# NoTricks_v2.net
KiCad netlist of a schematic drawn in EAGLE
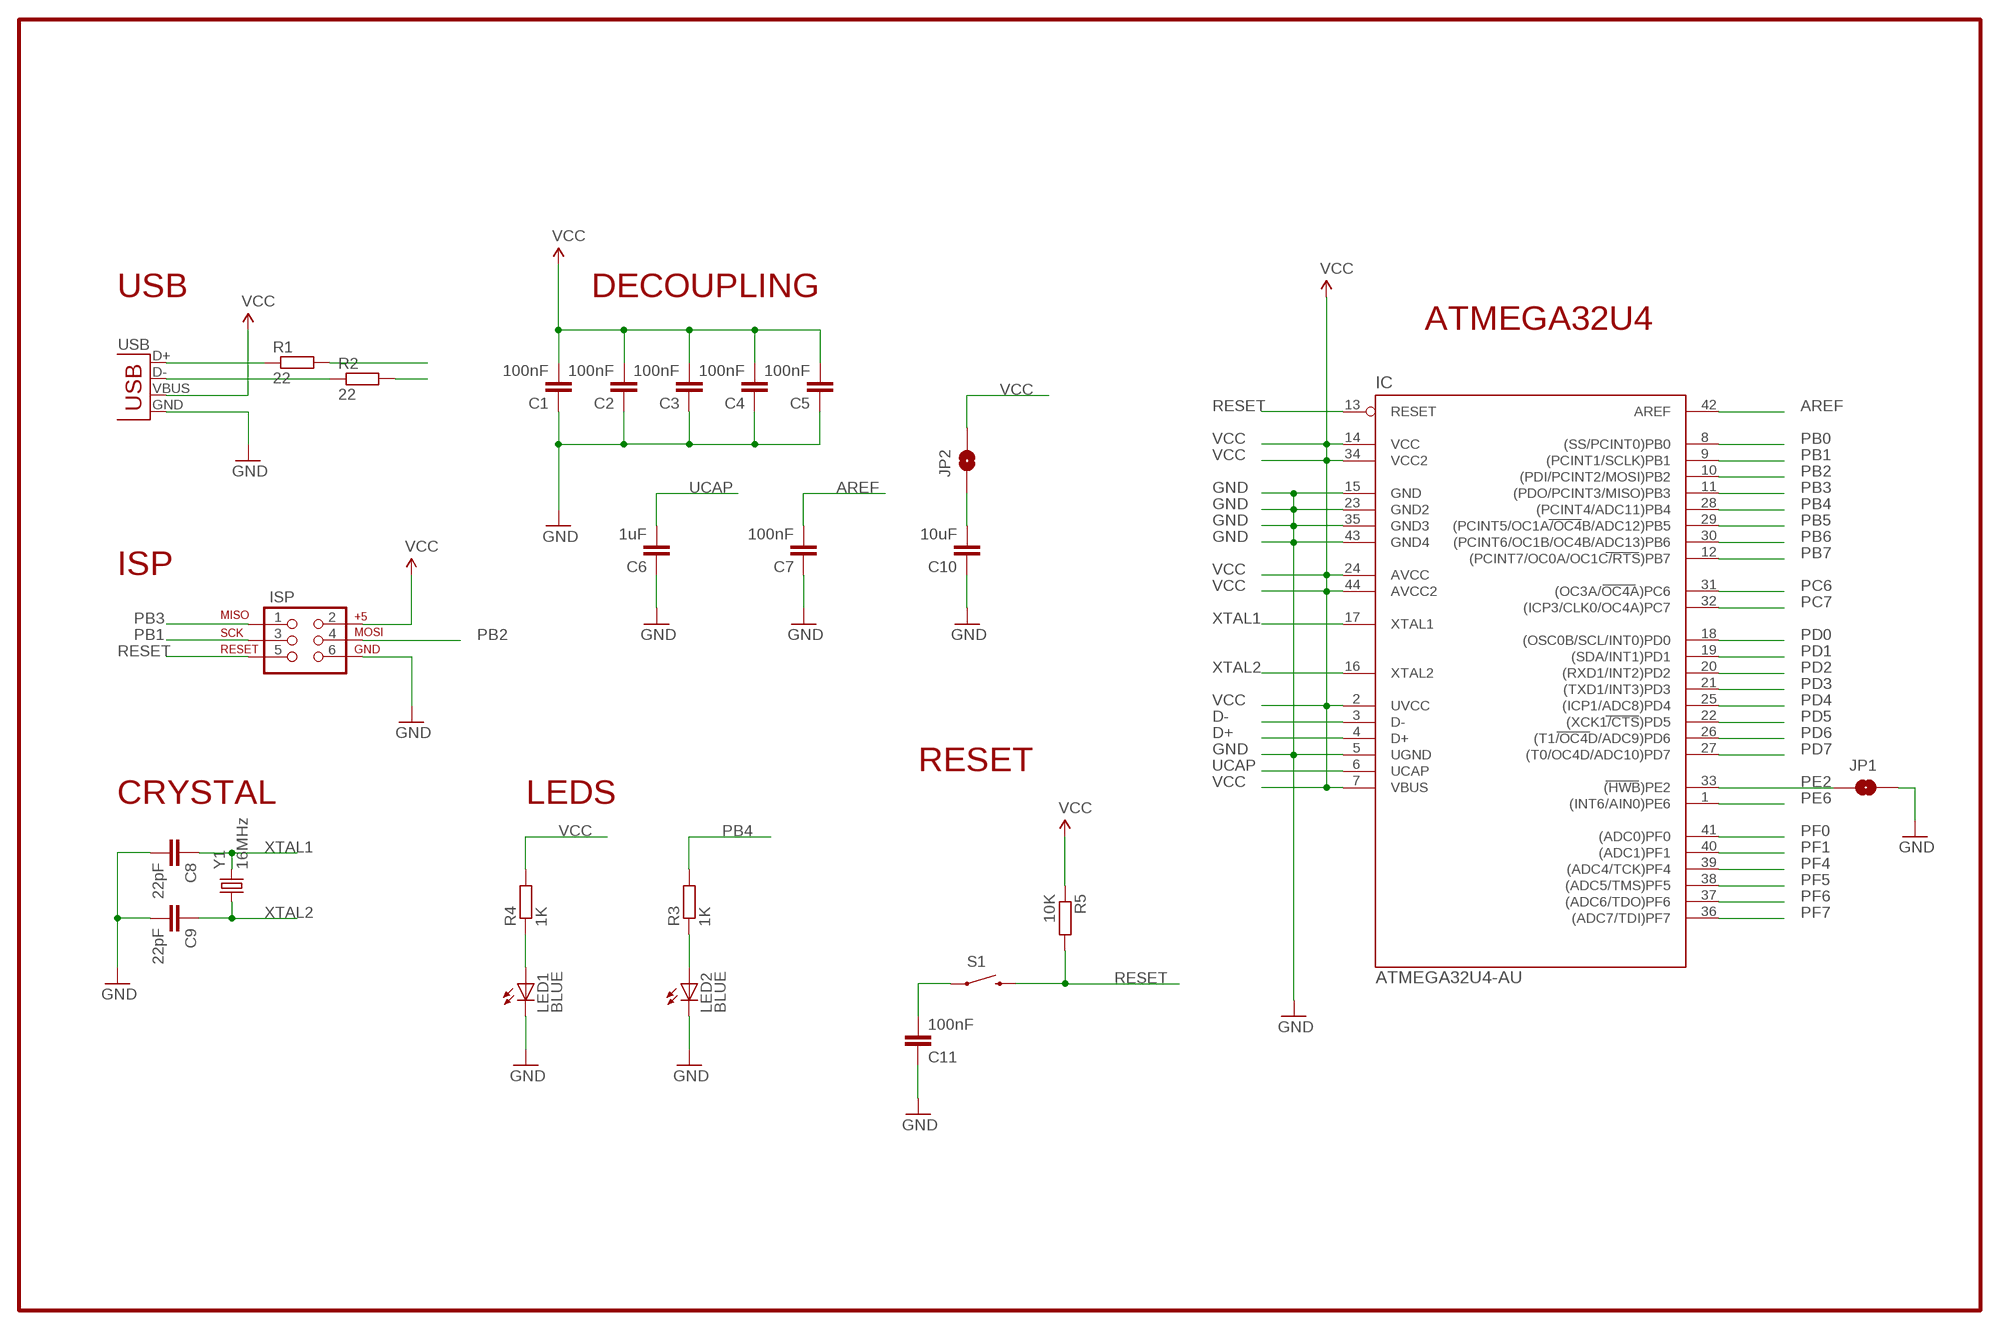
[diagram p0: schematic, sheet 1]

(export (version "E")
  (design (tool "Eeschema 10.0.6"))
  (components
    (comp (ref "C1")
      (value "100nF")
      (footprint "eagle-import:C0805")
      (libsource (lib "eagle-import") (part "C-EUC0805"))
    )
    (comp (ref "C2")
      (value "100nF")
      (footprint "eagle-import:C0805")
      (libsource (lib "eagle-import") (part "C-EUC0805"))
    )
    (comp (ref "C3")
      (value "100nF")
      (footprint "eagle-import:C0805")
      (libsource (lib "eagle-import") (part "C-EUC0805"))
    )
    (comp (ref "C4")
      (value "100nF")
      (footprint "eagle-import:C0805")
      (libsource (lib "eagle-import") (part "C-EUC0805"))
    )
    (comp (ref "C5")
      (value "100nF")
      (footprint "eagle-import:C0805")
      (libsource (lib "eagle-import") (part "C-EUC0805"))
    )
    (comp (ref "C6")
      (value "1uF")
      (footprint "eagle-import:C0805")
      (libsource (lib "eagle-import") (part "C-EUC0805"))
    )
    (comp (ref "C7")
      (value "100nF")
      (footprint "eagle-import:C0805")
      (libsource (lib "eagle-import") (part "C-EUC0805"))
    )
    (comp (ref "C8")
      (value "22pF")
      (footprint "eagle-import:C0805")
      (libsource (lib "eagle-import") (part "C-EUC0805"))
    )
    (comp (ref "C9")
      (value "22pF")
      (footprint "eagle-import:C0805")
      (libsource (lib "eagle-import") (part "C-EUC0805"))
    )
    (comp (ref "C10")
      (value "10uF")
      (footprint "eagle-import:C0805")
      (libsource (lib "eagle-import") (part "C-EUC0805"))
    )
    (comp (ref "C11")
      (value "100nF")
      (footprint "eagle-import:C0805")
      (libsource (lib "eagle-import") (part "C-EUC0805"))
    )
    (comp (ref "IC")
      (value "ATMEGA32U4-AU")
      (footprint "eagle-import:TQFP44")
      (libsource (lib "eagle-import") (part "ATMEGA32U4-AU"))
    )
    (comp (ref "ISP")
      (value "AVR_SPI_PRG_6PTH")
      (footprint "eagle-import:2X3")
      (libsource (lib "eagle-import") (part "AVR_SPI_PRG_6PTH"))
    )
    (comp (ref "JP1")
      (value "JUMPER-PAD-2-NO")
      (footprint "eagle-import:PAD-JUMPER-2-NO_NO_SILK")
      (libsource (lib "eagle-import") (part "JUMPER-PAD-2-NO"))
    )
    (comp (ref "JP2")
      (value "JUMPER-PAD-2-NO")
      (footprint "eagle-import:PAD-JUMPER-2-NO_NO_SILK")
      (libsource (lib "eagle-import") (part "JUMPER-PAD-2-NO"))
    )
    (comp (ref "LED1")
      (value "BLUE")
      (footprint "eagle-import:LED-1206")
      (libsource (lib "eagle-import") (part "LED1206"))
    )
    (comp (ref "LED2")
      (value "BLUE")
      (footprint "eagle-import:LED-1206")
      (libsource (lib "eagle-import") (part "LED1206"))
    )
    (comp (ref "R1")
      (value "22")
      (footprint "eagle-import:R0603")
      (libsource (lib "eagle-import") (part "R-EU_R0603"))
    )
    (comp (ref "R2")
      (value "22")
      (footprint "eagle-import:R0603")
      (libsource (lib "eagle-import") (part "R-EU_R0603"))
    )
    (comp (ref "R3")
      (value "1K")
      (footprint "eagle-import:R0603")
      (libsource (lib "eagle-import") (part "R-EU_R0603"))
    )
    (comp (ref "R4")
      (value "1K")
      (footprint "eagle-import:R0603")
      (libsource (lib "eagle-import") (part "R-EU_R0603"))
    )
    (comp (ref "R5")
      (value "10K")
      (footprint "eagle-import:R0603")
      (libsource (lib "eagle-import") (part "R-EU_R0603"))
    )
    (comp (ref "S1")
      (value "SWITCH-MOMENTARY-2SMD")
      (footprint "eagle-import:TACTILE-SWITCH-SMD")
      (libsource (lib "eagle-import") (part "SWITCH-MOMENTARY-2SMD"))
    )
    (comp (ref "USB")
      (value "USB-A-H")
      (footprint "eagle-import:USB-A-H")
      (libsource (lib "eagle-import") (part "USB-A-H"))
    )
    (comp (ref "Y1")
      (value "16MHz")
      (footprint "eagle-import:CRYSTAL-SMD-5X3")
      (libsource (lib "eagle-import") (part "CRYSTALCRYSTAL-SMD-5X3-12MHZ"))
    )
  )
  (nets
    (net (code "1") (name "/AREF") (class "Default")
      (node (ref "C7") (pin "2") (pinfunction "2_2") (pintype "passive"))
      (node (ref "IC") (pin "42") (pinfunction "AREF_42") (pintype "bidirectional"))
    )
    (net (code "2") (name "/D+") (class "Default")
      (node (ref "IC") (pin "4") (pinfunction "D+_4") (pintype "bidirectional"))
      (node (ref "R1") (pin "2") (pinfunction "2_2") (pintype "passive"))
    )
    (net (code "3") (name "/D-") (class "Default")
      (node (ref "IC") (pin "3") (pinfunction "D-_3") (pintype "bidirectional"))
      (node (ref "R2") (pin "2") (pinfunction "2_2") (pintype "passive"))
    )
    (net (code "4") (name "/PB0") (class "Default")
      (node (ref "IC") (pin "8") (pinfunction "(SS/PCINT0)PB0_8") (pintype "bidirectional"))
    )
    (net (code "5") (name "/PB1") (class "Default")
      (node (ref "IC") (pin "9") (pinfunction "(PCINT1/SCLK)PB1_9") (pintype "bidirectional"))
      (node (ref "ISP") (pin "3") (pinfunction "3_3") (pintype "passive"))
    )
    (net (code "6") (name "/PB2") (class "Default")
      (node (ref "IC") (pin "10") (pinfunction "(PDI/PCINT2/MOSI)PB2_10") (pintype "bidirectional"))
      (node (ref "ISP") (pin "4") (pinfunction "4_4") (pintype "passive"))
    )
    (net (code "7") (name "/PB3") (class "Default")
      (node (ref "IC") (pin "11") (pinfunction "(PDO/PCINT3/MISO)PB3_11") (pintype "bidirectional"))
      (node (ref "ISP") (pin "1") (pinfunction "1_1") (pintype "passive"))
    )
    (net (code "8") (name "/PB4") (class "Default")
      (node (ref "IC") (pin "28") (pinfunction "(PCINT4/ADC11)PB4_28") (pintype "bidirectional"))
      (node (ref "R3") (pin "2") (pinfunction "2_2") (pintype "passive"))
    )
    (net (code "9") (name "/PB5") (class "Default")
      (node (ref "IC") (pin "29") (pinfunction "(PCINT5/OC1A/OC4B/ADC12)PB5_29") (pintype "bidirectional"))
    )
    (net (code "10") (name "/PB6") (class "Default")
      (node (ref "IC") (pin "30") (pinfunction "(PCINT6/OC1B/OC4B/ADC13)PB6_30") (pintype "bidirectional"))
    )
    (net (code "11") (name "/PB7") (class "Default")
      (node (ref "IC") (pin "12") (pinfunction "(PCINT7/OC0A/OC1C/RTS)PB7_12") (pintype "bidirectional"))
    )
    (net (code "12") (name "/PC6") (class "Default")
      (node (ref "IC") (pin "31") (pinfunction "(OC3A/OC4A)PC6_31") (pintype "bidirectional"))
    )
    (net (code "13") (name "/PC7") (class "Default")
      (node (ref "IC") (pin "32") (pinfunction "(ICP3/CLK0/OC4A)PC7_32") (pintype "bidirectional"))
    )
    (net (code "14") (name "/PD0") (class "Default")
      (node (ref "IC") (pin "18") (pinfunction "(OSC0B/SCL/INT0)PD0_18") (pintype "bidirectional"))
    )
    (net (code "15") (name "/PD1") (class "Default")
      (node (ref "IC") (pin "19") (pinfunction "(SDA/INT1)PD1_19") (pintype "bidirectional"))
    )
    (net (code "16") (name "/PD2") (class "Default")
      (node (ref "IC") (pin "20") (pinfunction "(RXD1/INT2)PD2_20") (pintype "bidirectional"))
    )
    (net (code "17") (name "/PD3") (class "Default")
      (node (ref "IC") (pin "21") (pinfunction "(TXD1/INT3)PD3_21") (pintype "bidirectional"))
    )
    (net (code "18") (name "/PD4") (class "Default")
      (node (ref "IC") (pin "25") (pinfunction "(ICP1/ADC8)PD4_25") (pintype "bidirectional"))
    )
    (net (code "19") (name "/PD5") (class "Default")
      (node (ref "IC") (pin "22") (pinfunction "(XCK1/CTS)PD5_22") (pintype "bidirectional"))
    )
    (net (code "20") (name "/PD6") (class "Default")
      (node (ref "IC") (pin "26") (pinfunction "(T1/OC4D/ADC9)PD6_26") (pintype "bidirectional"))
    )
    (net (code "21") (name "/PD7") (class "Default")
      (node (ref "IC") (pin "27") (pinfunction "(T0/OC4D/ADC10)PD7_27") (pintype "bidirectional"))
    )
    (net (code "22") (name "/PE2") (class "Default")
      (node (ref "IC") (pin "33") (pinfunction "(HWB)PE2_33") (pintype "bidirectional"))
      (node (ref "JP1") (pin "1") (pinfunction "1_1") (pintype "passive"))
    )
    (net (code "23") (name "/PE6") (class "Default")
      (node (ref "IC") (pin "1") (pinfunction "(INT6/AIN0)PE6_1") (pintype "bidirectional"))
    )
    (net (code "24") (name "/PF0") (class "Default")
      (node (ref "IC") (pin "41") (pinfunction "(ADC0)PF0_41") (pintype "bidirectional"))
    )
    (net (code "25") (name "/PF1") (class "Default")
      (node (ref "IC") (pin "40") (pinfunction "(ADC1)PF1_40") (pintype "bidirectional"))
    )
    (net (code "26") (name "/PF4") (class "Default")
      (node (ref "IC") (pin "39") (pinfunction "(ADC4/TCK)PF4_39") (pintype "bidirectional"))
    )
    (net (code "27") (name "/PF5") (class "Default")
      (node (ref "IC") (pin "38") (pinfunction "(ADC5/TMS)PF5_38") (pintype "bidirectional"))
    )
    (net (code "28") (name "/PF6") (class "Default")
      (node (ref "IC") (pin "37") (pinfunction "(ADC6/TDO)PF6_37") (pintype "bidirectional"))
    )
    (net (code "29") (name "/PF7") (class "Default")
      (node (ref "IC") (pin "36") (pinfunction "(ADC7/TDI)PF7_36") (pintype "bidirectional"))
    )
    (net (code "30") (name "/RESET") (class "Default")
      (node (ref "IC") (pin "13") (pinfunction "RESET_13") (pintype "bidirectional"))
      (node (ref "ISP") (pin "5") (pinfunction "5_5") (pintype "passive"))
      (node (ref "R5") (pin "2") (pinfunction "2_2") (pintype "passive"))
      (node (ref "S1") (pin "3") (pinfunction "2_3") (pintype "passive"))
    )
    (net (code "31") (name "/UCAP") (class "Default")
      (node (ref "C6") (pin "2") (pinfunction "2_2") (pintype "passive"))
      (node (ref "IC") (pin "6") (pinfunction "UCAP_6") (pintype "bidirectional"))
    )
    (net (code "32") (name "/XTAL1") (class "Default")
      (node (ref "C8") (pin "1") (pinfunction "1_1") (pintype "passive"))
      (node (ref "IC") (pin "17") (pinfunction "XTAL1_17") (pintype "bidirectional"))
      (node (ref "Y1") (pin "3") (pinfunction "2_3") (pintype "passive"))
    )
    (net (code "33") (name "/XTAL2") (class "Default")
      (node (ref "C9") (pin "1") (pinfunction "1_1") (pintype "passive"))
      (node (ref "IC") (pin "16") (pinfunction "XTAL2_16") (pintype "bidirectional"))
      (node (ref "Y1") (pin "1") (pinfunction "1_1") (pintype "passive"))
    )
    (net (code "34") (name "GND") (class "Default")
      (node (ref "C1") (pin "1") (pinfunction "1_1") (pintype "passive"))
      (node (ref "C10") (pin "1") (pinfunction "1_1") (pintype "passive"))
      (node (ref "C11") (pin "1") (pinfunction "1_1") (pintype "passive"))
      (node (ref "C2") (pin "1") (pinfunction "1_1") (pintype "passive"))
      (node (ref "C3") (pin "1") (pinfunction "1_1") (pintype "passive"))
      (node (ref "C4") (pin "1") (pinfunction "1_1") (pintype "passive"))
      (node (ref "C5") (pin "1") (pinfunction "1_1") (pintype "passive"))
      (node (ref "C6") (pin "1") (pinfunction "1_1") (pintype "passive"))
      (node (ref "C7") (pin "1") (pinfunction "1_1") (pintype "passive"))
      (node (ref "C8") (pin "2") (pinfunction "2_2") (pintype "passive"))
      (node (ref "C9") (pin "2") (pinfunction "2_2") (pintype "passive"))
      (node (ref "IC") (pin "15") (pinfunction "GND_15") (pintype "bidirectional"))
      (node (ref "IC") (pin "23") (pinfunction "GND2_23") (pintype "bidirectional"))
      (node (ref "IC") (pin "35") (pinfunction "GND3_35") (pintype "bidirectional"))
      (node (ref "IC") (pin "43") (pinfunction "GND4_43") (pintype "bidirectional"))
      (node (ref "IC") (pin "5") (pinfunction "UGND_5") (pintype "bidirectional"))
      (node (ref "ISP") (pin "6") (pinfunction "6_6") (pintype "passive"))
      (node (ref "JP1") (pin "2") (pinfunction "2_2") (pintype "passive"))
      (node (ref "LED1") (pin "C") (pinfunction "C_C") (pintype "passive"))
      (node (ref "LED2") (pin "C") (pinfunction "C_C") (pintype "passive"))
      (node (ref "USB") (pin "GND") (pinfunction "GND_GND") (pintype "bidirectional"))
    )
    (net (code "35") (name "Net-(C10-Pad2)") (class "Default")
      (node (ref "C10") (pin "2") (pinfunction "2_2") (pintype "passive"))
      (node (ref "JP2") (pin "1") (pinfunction "1_1") (pintype "passive"))
    )
    (net (code "36") (name "Net-(C11-Pad2)") (class "Default")
      (node (ref "C11") (pin "2") (pinfunction "2_2") (pintype "passive"))
      (node (ref "S1") (pin "1") (pinfunction "1_1") (pintype "passive"))
    )
    (net (code "37") (name "Net-(LED1-PadA)") (class "Default")
      (node (ref "LED1") (pin "A") (pinfunction "A_A") (pintype "passive"))
      (node (ref "R4") (pin "1") (pinfunction "1_1") (pintype "passive"))
    )
    (net (code "38") (name "Net-(LED2-PadA)") (class "Default")
      (node (ref "LED2") (pin "A") (pinfunction "A_A") (pintype "passive"))
      (node (ref "R3") (pin "1") (pinfunction "1_1") (pintype "passive"))
    )
    (net (code "39") (name "Net-(R1-Pad1)") (class "Default")
      (node (ref "R1") (pin "1") (pinfunction "1_1") (pintype "passive"))
      (node (ref "USB") (pin "D+") (pinfunction "D+_D+") (pintype "bidirectional"))
    )
    (net (code "40") (name "Net-(R2-Pad1)") (class "Default")
      (node (ref "R2") (pin "1") (pinfunction "1_1") (pintype "passive"))
      (node (ref "USB") (pin "D-") (pinfunction "D-_D-") (pintype "bidirectional"))
    )
    (net (code "41") (name "VCC") (class "Default")
      (node (ref "C1") (pin "2") (pinfunction "2_2") (pintype "passive"))
      (node (ref "C2") (pin "2") (pinfunction "2_2") (pintype "passive"))
      (node (ref "C3") (pin "2") (pinfunction "2_2") (pintype "passive"))
      (node (ref "C4") (pin "2") (pinfunction "2_2") (pintype "passive"))
      (node (ref "C5") (pin "2") (pinfunction "2_2") (pintype "passive"))
      (node (ref "IC") (pin "14") (pinfunction "VCC_14") (pintype "bidirectional"))
      (node (ref "IC") (pin "2") (pinfunction "UVCC_2") (pintype "bidirectional"))
      (node (ref "IC") (pin "24") (pinfunction "AVCC_24") (pintype "bidirectional"))
      (node (ref "IC") (pin "34") (pinfunction "VCC2_34") (pintype "bidirectional"))
      (node (ref "IC") (pin "44") (pinfunction "AVCC2_44") (pintype "bidirectional"))
      (node (ref "IC") (pin "7") (pinfunction "VBUS_7") (pintype "bidirectional"))
      (node (ref "ISP") (pin "2") (pinfunction "2_2") (pintype "passive"))
      (node (ref "JP2") (pin "2") (pinfunction "2_2") (pintype "passive"))
      (node (ref "R4") (pin "2") (pinfunction "2_2") (pintype "passive"))
      (node (ref "R5") (pin "1") (pinfunction "1_1") (pintype "passive"))
      (node (ref "USB") (pin "VBUS") (pinfunction "VBUS_VBUS") (pintype "bidirectional"))
    )
  )
)
